# SCH_ESP32_red_MP3_card_2022-04-29.net
KiCad netlist of a schematic drawn in EasyEDA
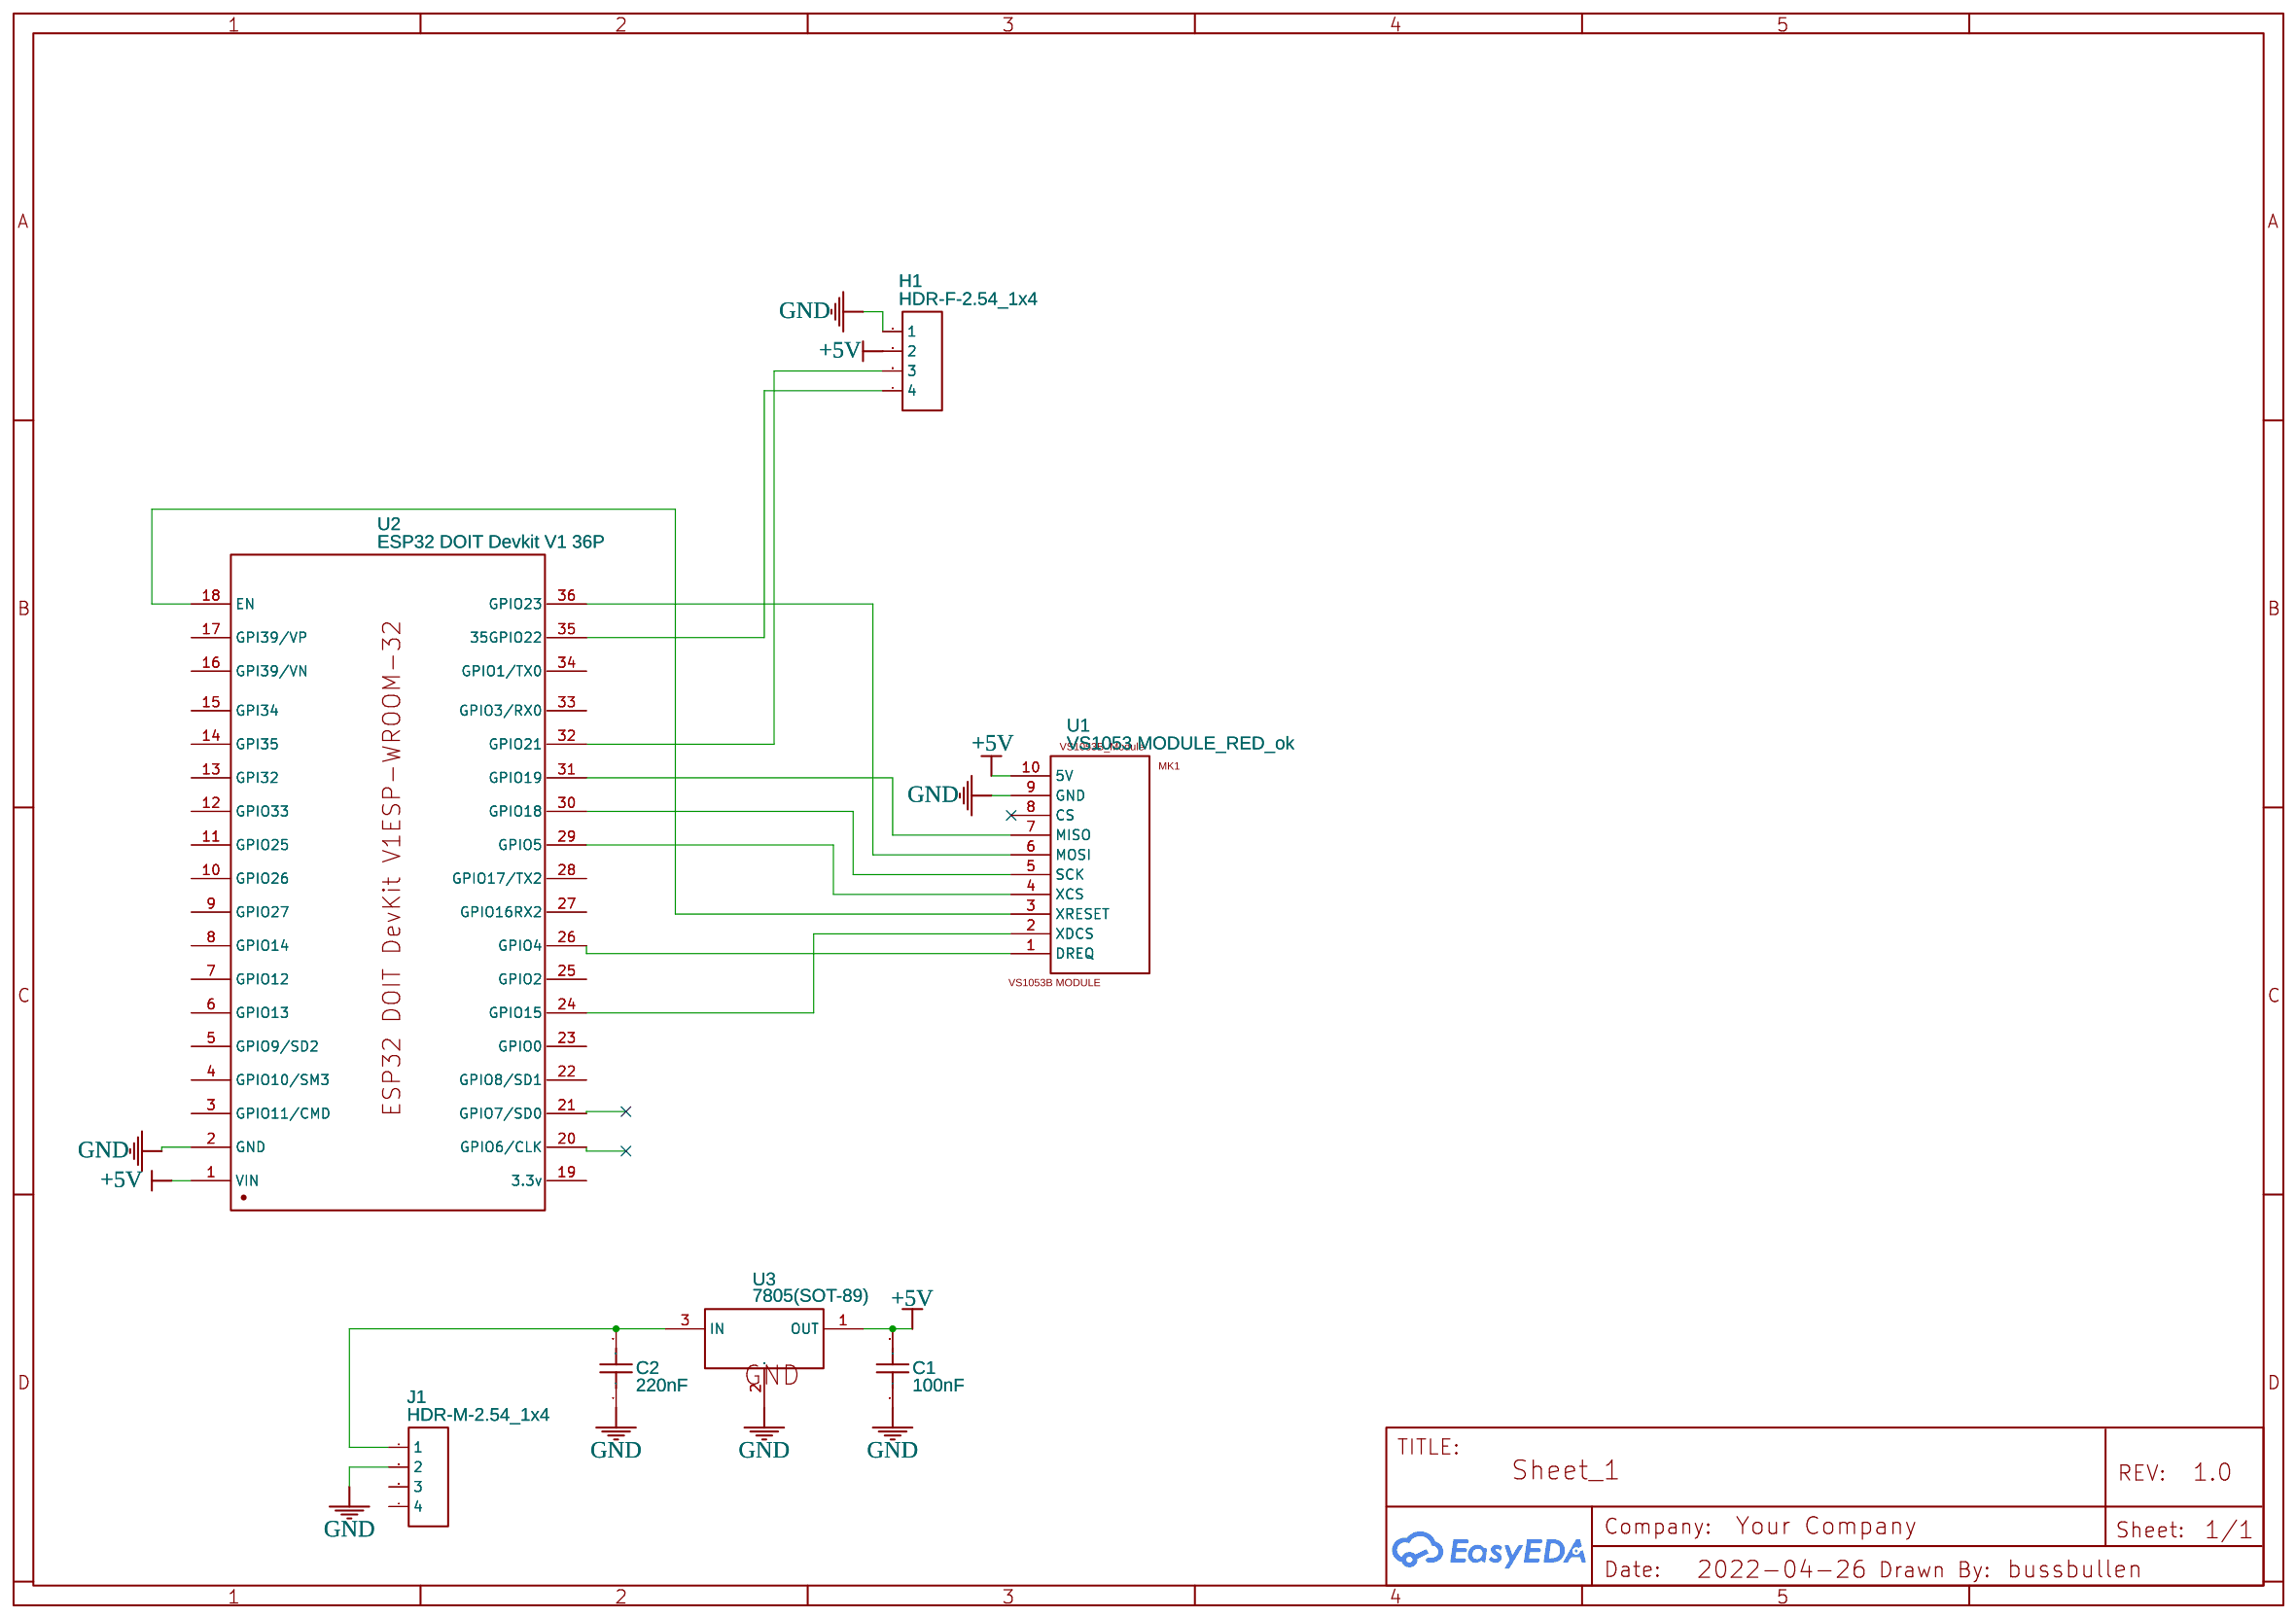
[diagram p0: schematic sheet]

(export (version "E")
  (design (tool "Eeschema 10.0.6"))
  (components
    (comp (ref "C1")
      (value "100nF")
      (fields
        (field (name "BOM_Manufacturer Part") "SMEC104J100M1")
        (field (name "BOM_Supplier Part") "C401095")
      )
      (libsource (lib "") (part "SMEC104J100M1"))
    )
    (comp (ref "C2")
      (value "220nF")
      (fields
        (field (name "BOM_Manufacturer Part") "SMEC224J100M2")
        (field (name "BOM_Supplier Part") "C401099")
      )
      (libsource (lib "") (part "SMEC224J100M2"))
    )
    (comp (ref "H1")
      (value "HDR-F-2.54_1x4")
      (fields (field (name "BOM_Supplier Part") "C225501"))
      (libsource (lib "") (part "HDR-F-2.54_1x4"))
    )
    (comp (ref "J1")
      (value "HDR-M-2.54_1x4")
      (fields (field (name "BOM_Supplier Part") "C124378"))
      (libsource (lib "") (part "HDR-M-2.54_1x4"))
    )
    (comp (ref "U1") (value "VS1053 MODULE_RED_ok") (libsource (lib "") (part "VS1053 MODULE_RED_ok")))
    (comp (ref "U2")
      (value "ESP32 DOIT Devkit V1 36P")
      (libsource (lib "") (part "ESP32 DOIT Devkit V1 36P"))
    )
    (comp (ref "U3")
      (value "7805(SOT-89)")
      (fields (field (name "BOM_Manufacturer Part") "CJ78L05") (field (name "BOM_Supplier Part") "C2079"))
      (libsource (lib "") (part "7805(SOT-89)"))
    )
  )
  (nets
    (net (code "1") (name "+5V") (class "Default")
      (node (ref "C1") (pin "2") (pinfunction "2_2") (pintype "unspecified"))
      (node (ref "H1") (pin "2") (pinfunction "2_2") (pintype "unspecified"))
      (node (ref "U1") (pin "10") (pinfunction "5V_10") (pintype "unspecified"))
      (node (ref "U2") (pin "1") (pinfunction "VIN_1") (pintype "unspecified"))
      (node (ref "U3") (pin "1") (pinfunction "OUT_1") (pintype "passive"))
    )
    (net (code "2") (name "GND") (class "Default")
      (node (ref "C1") (pin "1") (pinfunction "1_1") (pintype "unspecified"))
      (node (ref "C2") (pin "1") (pinfunction "1_1") (pintype "unspecified"))
      (node (ref "H1") (pin "1") (pinfunction "1_1") (pintype "unspecified"))
      (node (ref "J1") (pin "2") (pinfunction "2_2") (pintype "unspecified"))
      (node (ref "U1") (pin "9") (pinfunction "GND_9") (pintype "unspecified"))
      (node (ref "U2") (pin "2") (pinfunction "GND_2") (pintype "unspecified"))
      (node (ref "U3") (pin "2") (pinfunction "GND_2") (pintype "passive"))
    )
    (net (code "3") (name "Net-(U1-DREQ)") (class "Default")
      (node (ref "U1") (pin "1") (pinfunction "DREQ_1") (pintype "unspecified"))
      (node (ref "U2") (pin "26") (pinfunction "GPIO4_26") (pintype "unspecified"))
    )
    (net (code "4") (name "Net-(U1-MISO)") (class "Default")
      (node (ref "U1") (pin "7") (pinfunction "MISO_7") (pintype "unspecified"))
      (node (ref "U2") (pin "31") (pinfunction "GPIO19_31") (pintype "unspecified"))
    )
    (net (code "5") (name "Net-(U1-MOSI)") (class "Default")
      (node (ref "U1") (pin "6") (pinfunction "MOSI_6") (pintype "unspecified"))
      (node (ref "U2") (pin "36") (pinfunction "GPIO23_36") (pintype "unspecified"))
    )
    (net (code "6") (name "Net-(U1-SCK)") (class "Default")
      (node (ref "U1") (pin "5") (pinfunction "SCK_5") (pintype "unspecified"))
      (node (ref "U2") (pin "30") (pinfunction "GPIO18_30") (pintype "unspecified"))
    )
    (net (code "7") (name "Net-(U1-XCS)") (class "Default")
      (node (ref "U1") (pin "4") (pinfunction "XCS_4") (pintype "unspecified"))
      (node (ref "U2") (pin "29") (pinfunction "GPIO5_29") (pintype "unspecified"))
    )
    (net (code "8") (name "Net-(U1-XDCS)") (class "Default")
      (node (ref "U1") (pin "2") (pinfunction "XDCS_2") (pintype "unspecified"))
      (node (ref "U2") (pin "24") (pinfunction "GPIO15_24") (pintype "unspecified"))
    )
    (net (code "9") (name "Net-(U1-XRESET)") (class "Default")
      (node (ref "U1") (pin "3") (pinfunction "XRESET_3") (pintype "unspecified"))
      (node (ref "U2") (pin "18") (pinfunction "EN_18") (pintype "unspecified"))
    )
    (net (code "10") (name "Net-(U2-35GPIO22)") (class "Default")
      (node (ref "H1") (pin "4") (pinfunction "4_4") (pintype "unspecified"))
      (node (ref "U2") (pin "35") (pinfunction "35GPIO22_35") (pintype "unspecified"))
    )
    (net (code "11") (name "Net-(U2-GPIO21)") (class "Default")
      (node (ref "H1") (pin "3") (pinfunction "3_3") (pintype "unspecified"))
      (node (ref "U2") (pin "32") (pinfunction "GPIO21_32") (pintype "unspecified"))
    )
    (net (code "12") (name "Net-(U3-IN)") (class "Default")
      (node (ref "C2") (pin "2") (pinfunction "2_2") (pintype "unspecified"))
      (node (ref "J1") (pin "1") (pinfunction "1_1") (pintype "unspecified"))
      (node (ref "U3") (pin "3") (pinfunction "IN_3") (pintype "passive"))
    )
    (net (code "13") (name "unconnected-(J1-Pad3)") (class "Default")
      (node (ref "J1") (pin "3") (pinfunction "3_3") (pintype "unspecified"))
    )
    (net (code "14") (name "unconnected-(J1-Pad4)") (class "Default")
      (node (ref "J1") (pin "4") (pinfunction "4_4") (pintype "unspecified"))
    )
    (net (code "15") (name "unconnected-(U1-CS-Pad8)") (class "Default")
      (node (ref "U1") (pin "8") (pinfunction "CS_8") (pintype "unspecified+no_connect"))
    )
    (net (code "16") (name "unconnected-(U2-3.3v-Pad19)") (class "Default")
      (node (ref "U2") (pin "19") (pinfunction "3.3v_19") (pintype "unspecified"))
    )
    (net (code "17") (name "unconnected-(U2-GPI32-Pad13)") (class "Default")
      (node (ref "U2") (pin "13") (pinfunction "GPI32_13") (pintype "unspecified"))
    )
    (net (code "18") (name "unconnected-(U2-GPI34-Pad15)") (class "Default")
      (node (ref "U2") (pin "15") (pinfunction "GPI34_15") (pintype "unspecified"))
    )
    (net (code "19") (name "unconnected-(U2-GPI35-Pad14)") (class "Default")
      (node (ref "U2") (pin "14") (pinfunction "GPI35_14") (pintype "unspecified"))
    )
    (net (code "20") (name "unconnected-(U2-GPI39{slash}VN-Pad16)") (class "Default")
      (node (ref "U2") (pin "16") (pinfunction "GPI39/VN_16") (pintype "unspecified"))
    )
    (net (code "21") (name "unconnected-(U2-GPI39{slash}VP-Pad17)") (class "Default")
      (node (ref "U2") (pin "17") (pinfunction "GPI39/VP_17") (pintype "unspecified"))
    )
    (net (code "22") (name "unconnected-(U2-GPIO0-Pad23)") (class "Default")
      (node (ref "U2") (pin "23") (pinfunction "GPIO0_23") (pintype "unspecified"))
    )
    (net (code "23") (name "unconnected-(U2-GPIO1{slash}TX0-Pad34)") (class "Default")
      (node (ref "U2") (pin "34") (pinfunction "GPIO1/TX0_34") (pintype "unspecified"))
    )
    (net (code "24") (name "unconnected-(U2-GPIO2-Pad25)") (class "Default")
      (node (ref "U2") (pin "25") (pinfunction "GPIO2_25") (pintype "unspecified"))
    )
    (net (code "25") (name "unconnected-(U2-GPIO3{slash}RX0-Pad33)") (class "Default")
      (node (ref "U2") (pin "33") (pinfunction "GPIO3/RX0_33") (pintype "unspecified"))
    )
    (net (code "26") (name "unconnected-(U2-GPIO6{slash}CLK-Pad20)") (class "Default")
      (node (ref "U2") (pin "20") (pinfunction "GPIO6/CLK_20") (pintype "unspecified+no_connect"))
    )
    (net (code "27") (name "unconnected-(U2-GPIO7{slash}SD0-Pad21)") (class "Default")
      (node (ref "U2") (pin "21") (pinfunction "GPIO7/SD0_21") (pintype "unspecified+no_connect"))
    )
    (net (code "28") (name "unconnected-(U2-GPIO8{slash}SD1-Pad22)") (class "Default")
      (node (ref "U2") (pin "22") (pinfunction "GPIO8/SD1_22") (pintype "unspecified"))
    )
    (net (code "29") (name "unconnected-(U2-GPIO9{slash}SD2-Pad5)") (class "Default")
      (node (ref "U2") (pin "5") (pinfunction "GPIO9/SD2_5") (pintype "unspecified"))
    )
    (net (code "30") (name "unconnected-(U2-GPIO10{slash}SM3-Pad4)") (class "Default")
      (node (ref "U2") (pin "4") (pinfunction "GPIO10/SM3_4") (pintype "unspecified"))
    )
    (net (code "31") (name "unconnected-(U2-GPIO11{slash}CMD-Pad3)") (class "Default")
      (node (ref "U2") (pin "3") (pinfunction "GPIO11/CMD_3") (pintype "unspecified"))
    )
    (net (code "32") (name "unconnected-(U2-GPIO12-Pad7)") (class "Default")
      (node (ref "U2") (pin "7") (pinfunction "GPIO12_7") (pintype "unspecified"))
    )
    (net (code "33") (name "unconnected-(U2-GPIO13-Pad6)") (class "Default")
      (node (ref "U2") (pin "6") (pinfunction "GPIO13_6") (pintype "unspecified"))
    )
    (net (code "34") (name "unconnected-(U2-GPIO14-Pad8)") (class "Default")
      (node (ref "U2") (pin "8") (pinfunction "GPIO14_8") (pintype "unspecified"))
    )
    (net (code "35") (name "unconnected-(U2-GPIO16RX2-Pad27)") (class "Default")
      (node (ref "U2") (pin "27") (pinfunction "GPIO16RX2_27") (pintype "unspecified"))
    )
    (net (code "36") (name "unconnected-(U2-GPIO17{slash}TX2-Pad28)") (class "Default")
      (node (ref "U2") (pin "28") (pinfunction "GPIO17/TX2_28") (pintype "unspecified"))
    )
    (net (code "37") (name "unconnected-(U2-GPIO25-Pad11)") (class "Default")
      (node (ref "U2") (pin "11") (pinfunction "GPIO25_11") (pintype "unspecified"))
    )
    (net (code "38") (name "unconnected-(U2-GPIO26-Pad10)") (class "Default")
      (node (ref "U2") (pin "10") (pinfunction "GPIO26_10") (pintype "unspecified"))
    )
    (net (code "39") (name "unconnected-(U2-GPIO27-Pad9)") (class "Default")
      (node (ref "U2") (pin "9") (pinfunction "GPIO27_9") (pintype "unspecified"))
    )
    (net (code "40") (name "unconnected-(U2-GPIO33-Pad12)") (class "Default")
      (node (ref "U2") (pin "12") (pinfunction "GPIO33_12") (pintype "unspecified"))
    )
  )
)
